# CAN_3V3new.net
KiCad netlist of a schematic drawn in Altium Designer
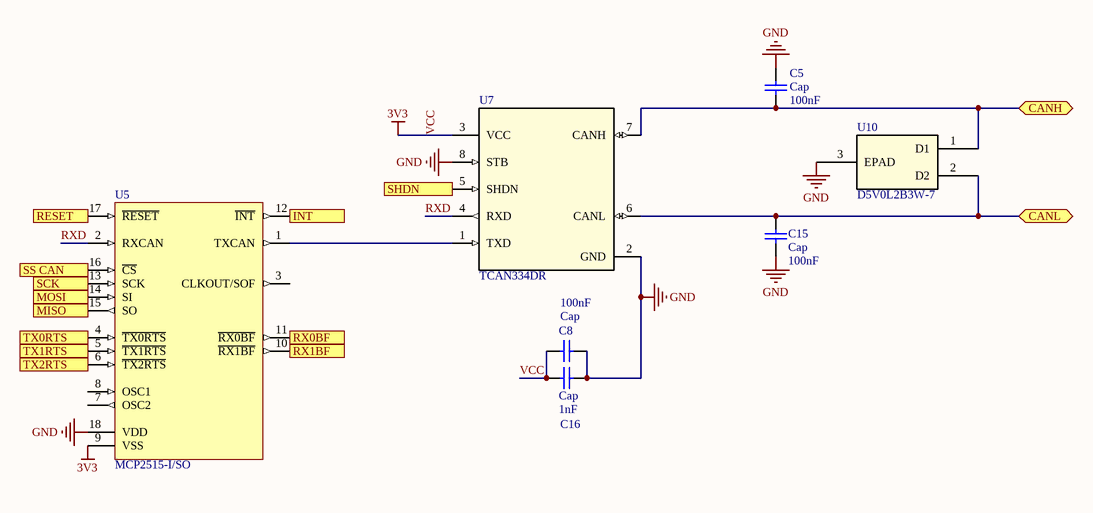
[diagram p0: CAN 3V3new.SchDoc]

(export (version "E")
  (design (tool "Eeschema 10.0.6"))
  (components
    (comp (ref "C5")
      (value "Cap")
      (footprint "1608[0603]")
      (description "Capacitor")
      (fields (field (name "ALTIUM_VALUE") "100nF") (field (name "PUBLISHER") "Altium Limited"))
      (libsource (lib "Miscellaneous Devices") (part "Cap"))
    )
    (comp (ref "C8")
      (value "Cap")
      (footprint "1608[0603]")
      (description "Capacitor")
      (fields (field (name "ALTIUM_VALUE") "100nF") (field (name "PUBLISHER") "Altium Limited"))
      (libsource (lib "Miscellaneous Devices") (part "Cap"))
    )
    (comp (ref "C15")
      (value "Cap")
      (footprint "1608[0603]")
      (description "Capacitor")
      (fields (field (name "ALTIUM_VALUE") "100nF") (field (name "PUBLISHER") "Altium Limited"))
      (libsource (lib "Miscellaneous Devices") (part "Cap"))
    )
    (comp (ref "C16")
      (value "Cap")
      (footprint "1608[0603]")
      (description "Capacitor")
      (fields (field (name "ALTIUM_VALUE") "1nF") (field (name "PUBLISHER") "Altium Limited"))
      (libsource (lib "Miscellaneous Devices") (part "Cap"))
    )
    (comp (ref "U5")
      (value "MCP2515-I/SO")
      (footprint "SOIC-SO18_L")
      (description "Stand-Alone CAN Controller With SPI Interface, 18-Pin SOIC, Industrial Temperature")
      (libsource (lib "Altium Content Vault") (part "COM-CAN-MCP2515-18"))
    )
    (comp (ref "U7")
      (value "TCAN334DR")
      (footprint "D0008A_N")
      (description "No Description Available")
      (fields
        (field (name "MANUFACTURER") "Texas Instruments")
        (field (name "COPYRIGHT") "Copyright (C) 2018 Accelerated Designs. All rights reserved")
      )
      (libsource (lib "CANTRAN3V3") (part "TCAN334DR"))
    )
    (comp (ref "U10")
      (value "D5V0L2B3W-7")
      (footprint "SOT-323_DIO")
      (description "No Description Available")
      (fields (field (name "COPYRIGHT") "Copyright (C) 2018 Accelerated Designs. All rights reserved"))
      (libsource (lib "D5V0L2B3W-7 library") (part "D5V0L2B3W-7"))
    )
  )
  (nets
    (net (code "1") (name "/CANH") (class "Default")
      (node (ref "C5") (pin "2") (pinfunction "2_2") (pintype "passive"))
      (node (ref "U10") (pin "1") (pinfunction "D1_1") (pintype "passive"))
      (node (ref "U7") (pin "7") (pinfunction "CANH_7") (pintype "bidirectional"))
    )
    (net (code "2") (name "/CANL") (class "Default")
      (node (ref "C15") (pin "2") (pinfunction "2_2") (pintype "passive"))
      (node (ref "U10") (pin "2") (pinfunction "D2_2") (pintype "passive"))
      (node (ref "U7") (pin "6") (pinfunction "CANL_6") (pintype "bidirectional"))
    )
    (net (code "3") (name "/INT") (class "Default")
      (node (ref "U5") (pin "12") (pinfunction "~{INT}_12") (pintype "output"))
    )
    (net (code "4") (name "/MISO") (class "Default")
      (node (ref "U5") (pin "15") (pinfunction "SO_15") (pintype "output"))
    )
    (net (code "5") (name "/MOSI") (class "Default")
      (node (ref "U5") (pin "14") (pinfunction "SI_14") (pintype "input"))
    )
    (net (code "6") (name "/RESET") (class "Default")
      (node (ref "U5") (pin "17") (pinfunction "~{RESET}_17") (pintype "input"))
    )
    (net (code "7") (name "/RX0BF") (class "Default")
      (node (ref "U5") (pin "11") (pinfunction "~{RX0BF}_11") (pintype "output"))
    )
    (net (code "8") (name "/RX1BF") (class "Default")
      (node (ref "U5") (pin "10") (pinfunction "~{RX1BF}_10") (pintype "output"))
    )
    (net (code "9") (name "/RXD") (class "Default")
      (node (ref "U5") (pin "2") (pinfunction "RXCAN_2") (pintype "input"))
      (node (ref "U7") (pin "4") (pinfunction "RXD_4") (pintype "output"))
    )
    (net (code "10") (name "/SCK") (class "Default")
      (node (ref "U5") (pin "13") (pinfunction "SCK_13") (pintype "input"))
    )
    (net (code "11") (name "/SHDN") (class "Default")
      (node (ref "U7") (pin "5") (pinfunction "SHDN_5") (pintype "input"))
    )
    (net (code "12") (name "/SS CAN") (class "Default")
      (node (ref "U5") (pin "16") (pinfunction "~{CS}_16") (pintype "input"))
    )
    (net (code "13") (name "/TX0RTS") (class "Default")
      (node (ref "U5") (pin "4") (pinfunction "~{TX0RTS}_4") (pintype "input"))
    )
    (net (code "14") (name "/TX1RTS") (class "Default")
      (node (ref "U5") (pin "5") (pinfunction "~{TX1RTS}_5") (pintype "input"))
    )
    (net (code "15") (name "/TX2RTS") (class "Default")
      (node (ref "U5") (pin "6") (pinfunction "~{TX2RTS}_6") (pintype "input"))
    )
    (net (code "16") (name "3V3") (class "Default")
      (node (ref "C16") (pin "2") (pinfunction "2_2") (pintype "passive"))
      (node (ref "C8") (pin "1") (pinfunction "1_1") (pintype "passive"))
      (node (ref "U5") (pin "9") (pinfunction "VSS_9") (pintype "power_in"))
      (node (ref "U7") (pin "3") (pinfunction "VCC_3") (pintype "power_in"))
    )
    (net (code "17") (name "GND") (class "Default")
      (node (ref "C15") (pin "1") (pinfunction "1_1") (pintype "passive"))
      (node (ref "C16") (pin "1") (pinfunction "1_1") (pintype "passive"))
      (node (ref "C5") (pin "1") (pinfunction "1_1") (pintype "passive"))
      (node (ref "C8") (pin "2") (pinfunction "2_2") (pintype "passive"))
      (node (ref "U10") (pin "3") (pinfunction "EPAD_3") (pintype "passive"))
      (node (ref "U5") (pin "18") (pinfunction "VDD_18") (pintype "power_in"))
      (node (ref "U7") (pin "2") (pinfunction "GND_2") (pintype "power_in"))
      (node (ref "U7") (pin "8") (pinfunction "STB_8") (pintype "input"))
    )
    (net (code "18") (name "Net-(U5-TXCAN)") (class "Default")
      (node (ref "U5") (pin "1") (pinfunction "TXCAN_1") (pintype "output"))
      (node (ref "U7") (pin "1") (pinfunction "TXD_1") (pintype "input"))
    )
    (net (code "19") (name "unconnected-(U5-CLKOUT{slash}SOF-Pad3)") (class "Default")
      (node (ref "U5") (pin "3") (pinfunction "CLKOUT/SOF_3") (pintype "output"))
    )
    (net (code "20") (name "unconnected-(U5-OSC1-Pad8)") (class "Default")
      (node (ref "U5") (pin "8") (pinfunction "OSC1_8") (pintype "input"))
    )
    (net (code "21") (name "unconnected-(U5-OSC2-Pad7)") (class "Default")
      (node (ref "U5") (pin "7") (pinfunction "OSC2_7") (pintype "output"))
    )
  )
)
